# BOARD.net
KiCad netlist of a schematic drawn in EAGLE
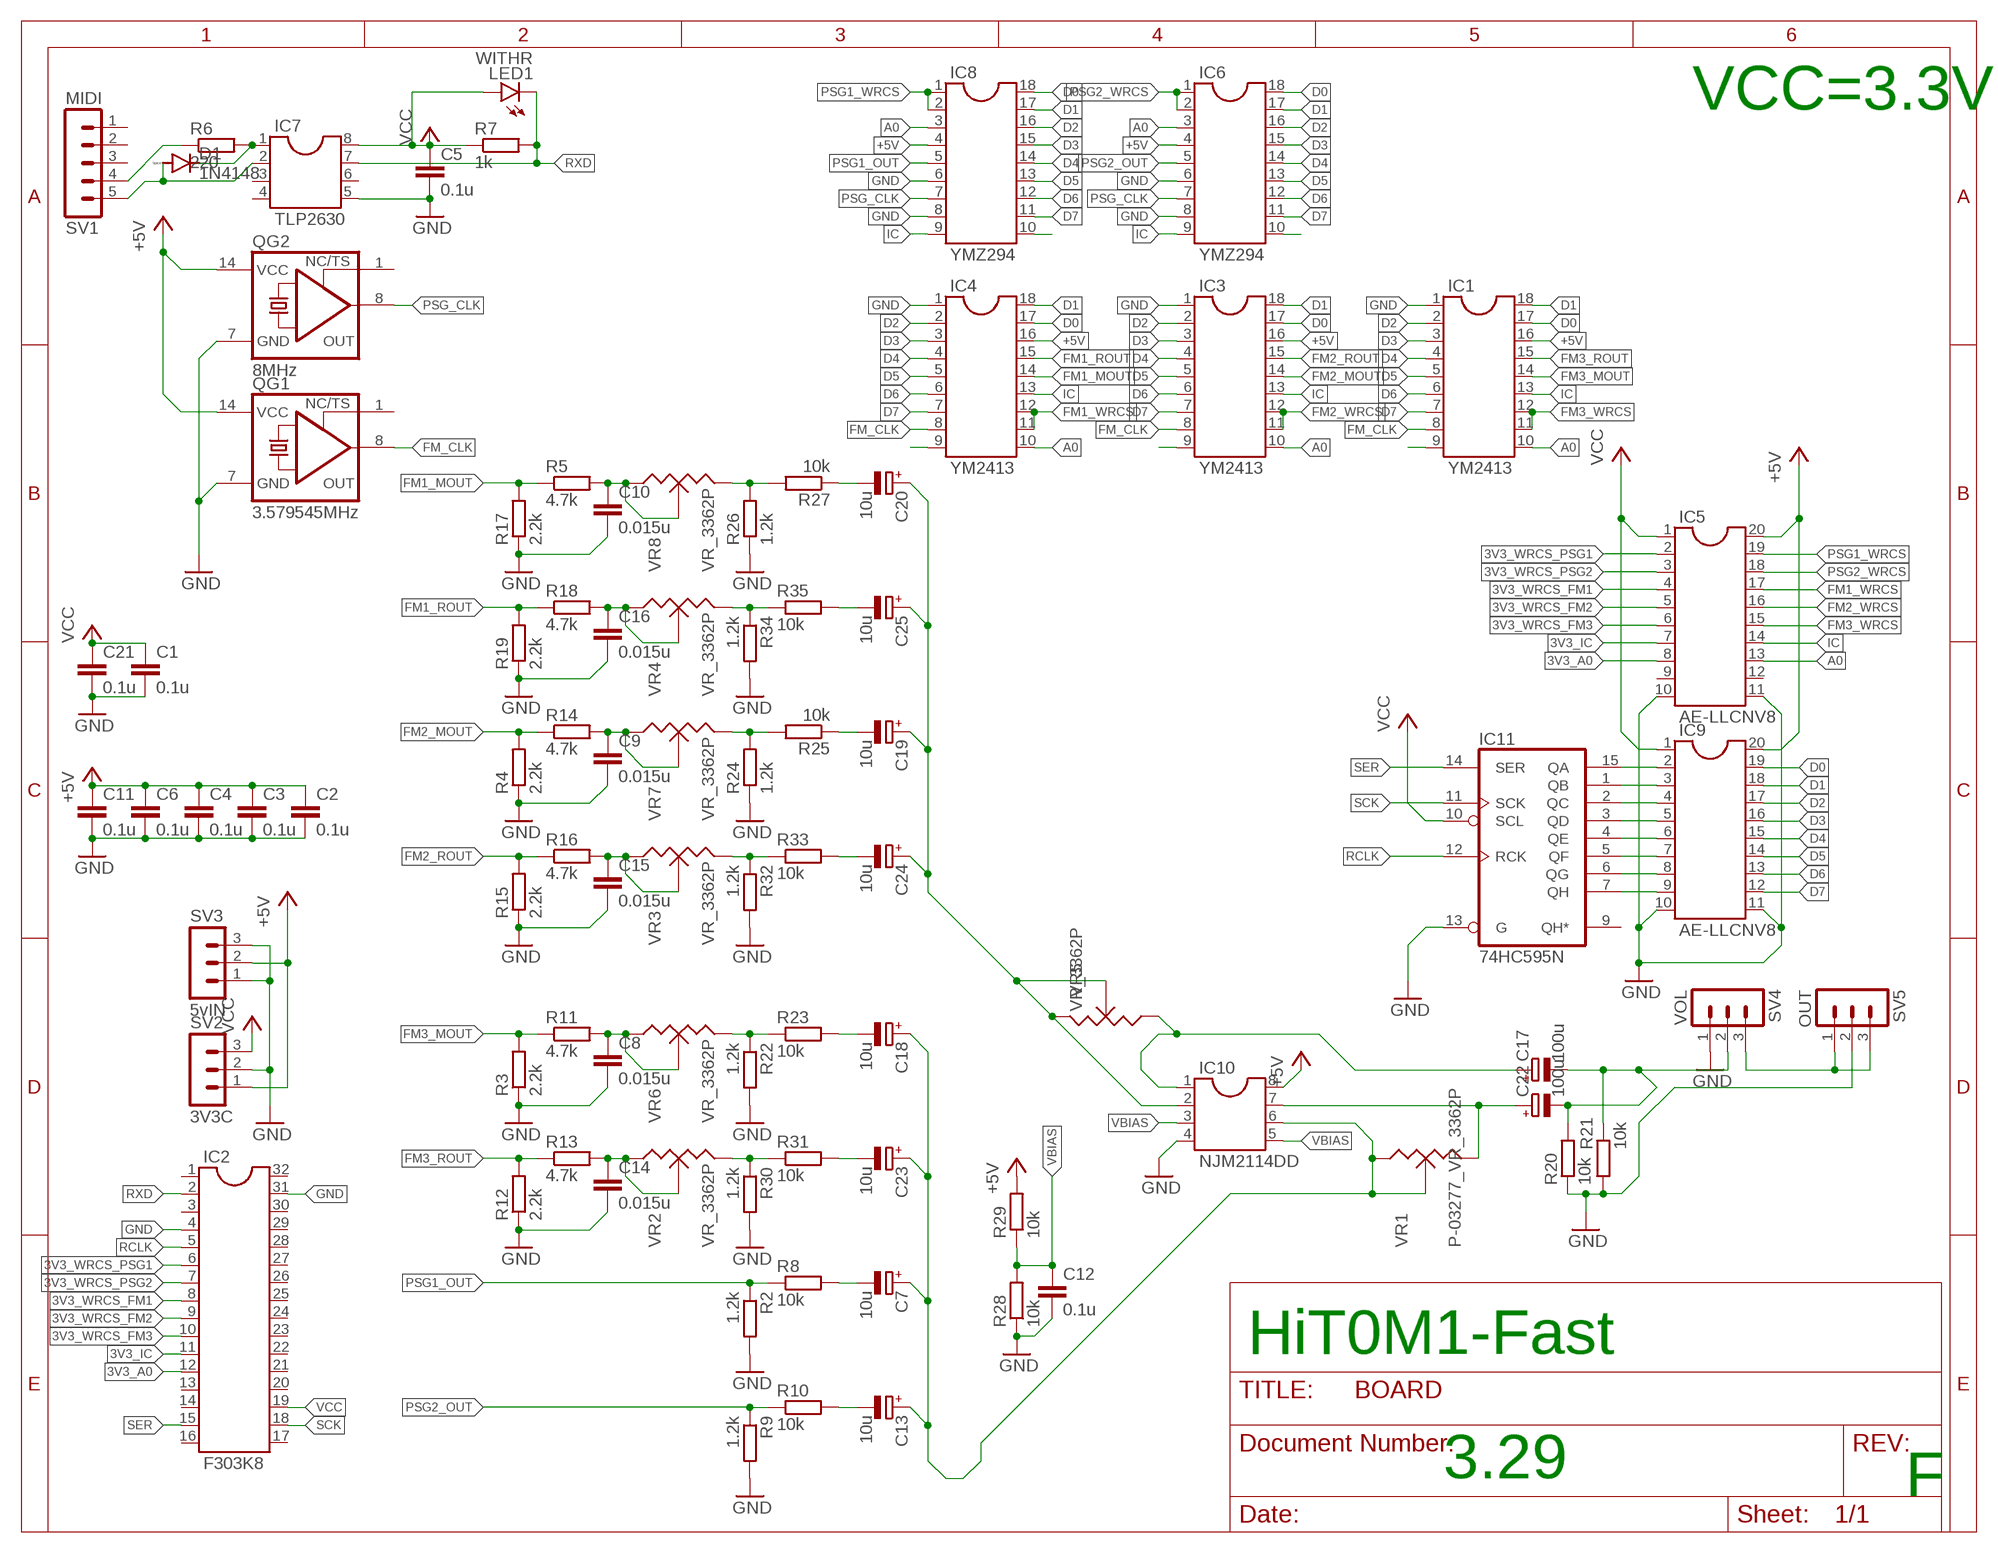
[diagram p0: schematic, sheet 1]

(export (version "E")
  (design (tool "Eeschema 10.0.6"))
  (components
    (comp (ref "C1")
      (value "0.1u")
      (footprint "eagle-import:C025-025X050")
      (libsource (lib "eagle-import") (part "C-EU025-025X050"))
    )
    (comp (ref "C2")
      (value "0.1u")
      (footprint "eagle-import:C025-025X050")
      (libsource (lib "eagle-import") (part "C-EU025-025X050"))
    )
    (comp (ref "C3")
      (value "0.1u")
      (footprint "eagle-import:C025-025X050")
      (libsource (lib "eagle-import") (part "C-EU025-025X050"))
    )
    (comp (ref "C4")
      (value "0.1u")
      (footprint "eagle-import:C025-025X050")
      (libsource (lib "eagle-import") (part "C-EU025-025X050"))
    )
    (comp (ref "C5")
      (value "0.1u")
      (footprint "eagle-import:C025-025X050")
      (libsource (lib "eagle-import") (part "C-EU025-025X050"))
    )
    (comp (ref "C6")
      (value "0.1u")
      (footprint "eagle-import:C025-025X050")
      (libsource (lib "eagle-import") (part "C-EU025-025X050"))
    )
    (comp (ref "C7")
      (value "10u")
      (footprint "eagle-import:E2,5-6E")
      (libsource (lib "eagle-import") (part "CPOL-EUE2,5-6E"))
    )
    (comp (ref "C8")
      (value "0.015u")
      (footprint "eagle-import:C050-025X075")
      (libsource (lib "eagle-import") (part "C-EU050-025X075"))
    )
    (comp (ref "C9")
      (value "0.015u")
      (footprint "eagle-import:C050-025X075")
      (libsource (lib "eagle-import") (part "C-EU050-025X075"))
    )
    (comp (ref "C10")
      (value "0.015u")
      (footprint "eagle-import:C050-025X075")
      (libsource (lib "eagle-import") (part "C-EU050-025X075"))
    )
    (comp (ref "C11")
      (value "0.1u")
      (footprint "eagle-import:C025-025X050")
      (libsource (lib "eagle-import") (part "C-EU025-025X050"))
    )
    (comp (ref "C12")
      (value "0.1u")
      (footprint "eagle-import:C025-025X050")
      (libsource (lib "eagle-import") (part "C-EU025-025X050"))
    )
    (comp (ref "C13")
      (value "10u")
      (footprint "eagle-import:E2,5-6E")
      (libsource (lib "eagle-import") (part "CPOL-EUE2,5-6E"))
    )
    (comp (ref "C14")
      (value "0.015u")
      (footprint "eagle-import:C050-025X075")
      (libsource (lib "eagle-import") (part "C-EU050-025X075"))
    )
    (comp (ref "C15")
      (value "0.015u")
      (footprint "eagle-import:C050-025X075")
      (libsource (lib "eagle-import") (part "C-EU050-025X075"))
    )
    (comp (ref "C16")
      (value "0.015u")
      (footprint "eagle-import:C050-025X075")
      (libsource (lib "eagle-import") (part "C-EU050-025X075"))
    )
    (comp (ref "C17")
      (value "100u")
      (footprint "eagle-import:E2,5-6E")
      (libsource (lib "eagle-import") (part "CPOL-EUE2,5-6E"))
    )
    (comp (ref "C18")
      (value "10u")
      (footprint "eagle-import:E2,5-6E")
      (libsource (lib "eagle-import") (part "CPOL-EUE2,5-6E"))
    )
    (comp (ref "C19")
      (value "10u")
      (footprint "eagle-import:E2,5-6E")
      (libsource (lib "eagle-import") (part "CPOL-EUE2,5-6E"))
    )
    (comp (ref "C20")
      (value "10u")
      (footprint "eagle-import:E2,5-6E")
      (libsource (lib "eagle-import") (part "CPOL-EUE2,5-6E"))
    )
    (comp (ref "C21")
      (value "0.1u")
      (footprint "eagle-import:C025-025X050")
      (libsource (lib "eagle-import") (part "C-EU025-025X050"))
    )
    (comp (ref "C22")
      (value "100u")
      (footprint "eagle-import:E2,5-6E")
      (libsource (lib "eagle-import") (part "CPOL-EUE2,5-6E"))
    )
    (comp (ref "C23")
      (value "10u")
      (footprint "eagle-import:E2,5-6E")
      (libsource (lib "eagle-import") (part "CPOL-EUE2,5-6E"))
    )
    (comp (ref "C24")
      (value "10u")
      (footprint "eagle-import:E2,5-6E")
      (libsource (lib "eagle-import") (part "CPOL-EUE2,5-6E"))
    )
    (comp (ref "C25")
      (value "10u")
      (footprint "eagle-import:E2,5-6E")
      (libsource (lib "eagle-import") (part "CPOL-EUE2,5-6E"))
    )
    (comp (ref "D1")
      (value "1N4148")
      (footprint "eagle-import:DO35-7")
      (libsource (lib "eagle-import") (part "1N4148DO35-7"))
    )
    (comp (ref "IC1")
      (value "YM2413")
      (footprint "eagle-import:SOCKET-18")
      (libsource (lib "eagle-import") (part "DIL18S"))
    )
    (comp (ref "IC2")
      (value "F303K8")
      (footprint "eagle-import:DIL32")
      (libsource (lib "eagle-import") (part "DIL32"))
    )
    (comp (ref "IC3")
      (value "YM2413")
      (footprint "eagle-import:SOCKET-18")
      (libsource (lib "eagle-import") (part "DIL18S"))
    )
    (comp (ref "IC4")
      (value "YM2413")
      (footprint "eagle-import:SOCKET-18")
      (libsource (lib "eagle-import") (part "DIL18S"))
    )
    (comp (ref "IC5")
      (value "AE-LLCNV8")
      (footprint "eagle-import:SOCKET-20")
      (libsource (lib "eagle-import") (part "DIL20S"))
    )
    (comp (ref "IC6")
      (value "YMZ294")
      (footprint "eagle-import:SOCKET-18")
      (libsource (lib "eagle-import") (part "DIL18S"))
    )
    (comp (ref "IC7")
      (value "TLP2630")
      (footprint "eagle-import:SOCKET-08")
      (libsource (lib "eagle-import") (part "DIL8S"))
    )
    (comp (ref "IC8")
      (value "YMZ294")
      (footprint "eagle-import:SOCKET-18")
      (libsource (lib "eagle-import") (part "DIL18S"))
    )
    (comp (ref "IC9")
      (value "AE-LLCNV8")
      (footprint "eagle-import:SOCKET-20")
      (libsource (lib "eagle-import") (part "DIL20S"))
    )
    (comp (ref "IC10")
      (value "NJM2114DD")
      (footprint "eagle-import:SOCKET-08")
      (libsource (lib "eagle-import") (part "DIL8S"))
    )
    (comp (ref "IC11")
      (value "74HC595N")
      (footprint "eagle-import:DIL16")
      (libsource (lib "eagle-import") (part "74595NHC"))
    )
    (comp (ref "LED1")
      (value "WITHR")
      (footprint "eagle-import:LED3MM")
      (libsource (lib "eagle-import") (part "LED3MM"))
    )
    (comp (ref "QG1")
      (value "3.579545MHz")
      (footprint "eagle-import:DIL14S")
      (libsource (lib "eagle-import") (part "XO-14"))
    )
    (comp (ref "QG2")
      (value "8MHz")
      (footprint "eagle-import:DIL14S")
      (libsource (lib "eagle-import") (part "XO-14"))
    )
    (comp (ref "R2")
      (value "1.2k")
      (footprint "eagle-import:0207_2V")
      (libsource (lib "eagle-import") (part "R-EU_0207/2V"))
    )
    (comp (ref "R3")
      (value "2.2k")
      (footprint "eagle-import:0207_2V")
      (libsource (lib "eagle-import") (part "R-EU_0207/2V"))
    )
    (comp (ref "R4")
      (value "2.2k")
      (footprint "eagle-import:0207_2V")
      (libsource (lib "eagle-import") (part "R-EU_0207/2V"))
    )
    (comp (ref "R5")
      (value "4.7k")
      (footprint "eagle-import:0207_2V")
      (libsource (lib "eagle-import") (part "R-EU_0207/2V"))
    )
    (comp (ref "R6")
      (value "220")
      (footprint "eagle-import:0207_2V")
      (libsource (lib "eagle-import") (part "R-EU_0207/2V"))
    )
    (comp (ref "R7")
      (value "1k")
      (footprint "eagle-import:0207_2V")
      (libsource (lib "eagle-import") (part "R-EU_0207/2V"))
    )
    (comp (ref "R8")
      (value "10k")
      (footprint "eagle-import:0207_2V")
      (libsource (lib "eagle-import") (part "R-EU_0207/2V"))
    )
    (comp (ref "R9")
      (value "1.2k")
      (footprint "eagle-import:0207_2V")
      (libsource (lib "eagle-import") (part "R-EU_0207/2V"))
    )
    (comp (ref "R10")
      (value "10k")
      (footprint "eagle-import:0207_2V")
      (libsource (lib "eagle-import") (part "R-EU_0207/2V"))
    )
    (comp (ref "R11")
      (value "4.7k")
      (footprint "eagle-import:0207_2V")
      (libsource (lib "eagle-import") (part "R-EU_0207/2V"))
    )
    (comp (ref "R12")
      (value "2.2k")
      (footprint "eagle-import:0207_2V")
      (libsource (lib "eagle-import") (part "R-EU_0207/2V"))
    )
    (comp (ref "R13")
      (value "4.7k")
      (footprint "eagle-import:0207_2V")
      (libsource (lib "eagle-import") (part "R-EU_0207/2V"))
    )
    (comp (ref "R14")
      (value "4.7k")
      (footprint "eagle-import:0207_2V")
      (libsource (lib "eagle-import") (part "R-EU_0207/2V"))
    )
    (comp (ref "R15")
      (value "2.2k")
      (footprint "eagle-import:0207_2V")
      (libsource (lib "eagle-import") (part "R-EU_0207/2V"))
    )
    (comp (ref "R16")
      (value "4.7k")
      (footprint "eagle-import:0207_2V")
      (libsource (lib "eagle-import") (part "R-EU_0207/2V"))
    )
    (comp (ref "R17")
      (value "2.2k")
      (footprint "eagle-import:0207_2V")
      (libsource (lib "eagle-import") (part "R-EU_0207/2V"))
    )
    (comp (ref "R18")
      (value "4.7k")
      (footprint "eagle-import:0207_2V")
      (libsource (lib "eagle-import") (part "R-EU_0207/2V"))
    )
    (comp (ref "R19")
      (value "2.2k")
      (footprint "eagle-import:0207_2V")
      (libsource (lib "eagle-import") (part "R-EU_0207/2V"))
    )
    (comp (ref "R20")
      (value "10k")
      (footprint "eagle-import:0207_2V")
      (libsource (lib "eagle-import") (part "R-EU_0207/2V"))
    )
    (comp (ref "R21")
      (value "10k")
      (footprint "eagle-import:0207_2V")
      (libsource (lib "eagle-import") (part "R-EU_0207/2V"))
    )
    (comp (ref "R22")
      (value "1.2k")
      (footprint "eagle-import:0207_2V")
      (libsource (lib "eagle-import") (part "R-EU_0207/2V"))
    )
    (comp (ref "R23")
      (value "10k")
      (footprint "eagle-import:0207_2V")
      (libsource (lib "eagle-import") (part "R-EU_0207/2V"))
    )
    (comp (ref "R24")
      (value "1.2k")
      (footprint "eagle-import:0207_2V")
      (libsource (lib "eagle-import") (part "R-EU_0207/2V"))
    )
    (comp (ref "R25")
      (value "10k")
      (footprint "eagle-import:0207_2V")
      (libsource (lib "eagle-import") (part "R-EU_0207/2V"))
    )
    (comp (ref "R26")
      (value "1.2k")
      (footprint "eagle-import:0207_2V")
      (libsource (lib "eagle-import") (part "R-EU_0207/2V"))
    )
    (comp (ref "R27")
      (value "10k")
      (footprint "eagle-import:0207_2V")
      (libsource (lib "eagle-import") (part "R-EU_0207/2V"))
    )
    (comp (ref "R28")
      (value "10k")
      (footprint "eagle-import:0207_2V")
      (libsource (lib "eagle-import") (part "R-EU_0207/2V"))
    )
    (comp (ref "R29")
      (value "10k")
      (footprint "eagle-import:0207_2V")
      (libsource (lib "eagle-import") (part "R-EU_0207/2V"))
    )
    (comp (ref "R30")
      (value "1.2k")
      (footprint "eagle-import:0207_2V")
      (libsource (lib "eagle-import") (part "R-EU_0207/2V"))
    )
    (comp (ref "R31")
      (value "10k")
      (footprint "eagle-import:0207_2V")
      (libsource (lib "eagle-import") (part "R-EU_0207/2V"))
    )
    (comp (ref "R32")
      (value "1.2k")
      (footprint "eagle-import:0207_2V")
      (libsource (lib "eagle-import") (part "R-EU_0207/2V"))
    )
    (comp (ref "R33")
      (value "10k")
      (footprint "eagle-import:0207_2V")
      (libsource (lib "eagle-import") (part "R-EU_0207/2V"))
    )
    (comp (ref "R34")
      (value "1.2k")
      (footprint "eagle-import:0207_2V")
      (libsource (lib "eagle-import") (part "R-EU_0207/2V"))
    )
    (comp (ref "R35")
      (value "10k")
      (footprint "eagle-import:0207_2V")
      (libsource (lib "eagle-import") (part "R-EU_0207/2V"))
    )
    (comp (ref "SV1")
      (value "MIDI")
      (footprint "eagle-import:MA05-1")
      (libsource (lib "eagle-import") (part "MA05-1"))
    )
    (comp (ref "SV2")
      (value "3V3C")
      (footprint "eagle-import:MA03-1")
      (libsource (lib "eagle-import") (part "MA03-1"))
    )
    (comp (ref "SV3")
      (value "5vIN")
      (footprint "eagle-import:MA03-1")
      (libsource (lib "eagle-import") (part "MA03-1"))
    )
    (comp (ref "SV4")
      (value "VOL")
      (footprint "eagle-import:MA03-1")
      (libsource (lib "eagle-import") (part "MA03-1"))
    )
    (comp (ref "SV5")
      (value "OUT")
      (footprint "eagle-import:MA03-1")
      (libsource (lib "eagle-import") (part "MA03-1"))
    )
    (comp (ref "VR1")
      (value "P-03277_VR_3362P")
      (footprint "eagle-import:VR_3362P")
      (libsource (lib "eagle-import") (part "P-03277_VR_3362P"))
    )
    (comp (ref "VR2")
      (value "VR_3362P")
      (footprint "eagle-import:VR_3362P")
      (libsource (lib "eagle-import") (part "P-03277_VR_3362P"))
    )
    (comp (ref "VR3")
      (value "VR_3362P")
      (footprint "eagle-import:VR_3362P")
      (libsource (lib "eagle-import") (part "P-03277_VR_3362P"))
    )
    (comp (ref "VR4")
      (value "VR_3362P")
      (footprint "eagle-import:VR_3362P")
      (libsource (lib "eagle-import") (part "P-03277_VR_3362P"))
    )
    (comp (ref "VR5")
      (value "VR_3362P")
      (footprint "eagle-import:VR_3362P")
      (libsource (lib "eagle-import") (part "P-03277_VR_3362P"))
    )
    (comp (ref "VR6")
      (value "VR_3362P")
      (footprint "eagle-import:VR_3362P")
      (libsource (lib "eagle-import") (part "P-03277_VR_3362P"))
    )
    (comp (ref "VR7")
      (value "VR_3362P")
      (footprint "eagle-import:VR_3362P")
      (libsource (lib "eagle-import") (part "P-03277_VR_3362P"))
    )
    (comp (ref "VR8")
      (value "VR_3362P")
      (footprint "eagle-import:VR_3362P")
      (libsource (lib "eagle-import") (part "P-03277_VR_3362P"))
    )
  )
  (nets
    (net (code "1") (name "+5V") (class "Default")
      (node (ref "C11") (pin "1") (pinfunction "1_1") (pintype "passive"))
      (node (ref "C2") (pin "1") (pinfunction "1_1") (pintype "passive"))
      (node (ref "C3") (pin "1") (pinfunction "1_1") (pintype "passive"))
      (node (ref "C4") (pin "1") (pinfunction "1_1") (pintype "passive"))
      (node (ref "C6") (pin "1") (pinfunction "1_1") (pintype "passive"))
      (node (ref "IC1") (pin "16") (pinfunction "16_16") (pintype "passive"))
      (node (ref "IC10") (pin "8") (pinfunction "8_8") (pintype "passive"))
      (node (ref "IC3") (pin "16") (pinfunction "16_16") (pintype "passive"))
      (node (ref "IC4") (pin "16") (pinfunction "16_16") (pintype "passive"))
      (node (ref "IC5") (pin "20") (pinfunction "20_20") (pintype "passive"))
      (node (ref "IC6") (pin "4") (pinfunction "4_4") (pintype "passive"))
      (node (ref "IC8") (pin "4") (pinfunction "4_4") (pintype "passive"))
      (node (ref "IC9") (pin "20") (pinfunction "20_20") (pintype "passive"))
      (node (ref "QG1") (pin "14") (pinfunction "VCC_14") (pintype "power_in"))
      (node (ref "QG2") (pin "14") (pinfunction "VCC_14") (pintype "power_in"))
      (node (ref "R29") (pin "2") (pinfunction "2_2") (pintype "passive"))
      (node (ref "SV2") (pin "1") (pinfunction "1_1") (pintype "passive"))
      (node (ref "SV3") (pin "2") (pinfunction "2_2") (pintype "passive"))
    )
    (net (code "2") (name "3V3_A0") (class "Default")
      (node (ref "IC2") (pin "12") (pinfunction "12_12") (pintype "passive"))
      (node (ref "IC5") (pin "8") (pinfunction "8_8") (pintype "passive"))
    )
    (net (code "3") (name "3V3_IC") (class "Default")
      (node (ref "IC2") (pin "11") (pinfunction "11_11") (pintype "passive"))
      (node (ref "IC5") (pin "7") (pinfunction "7_7") (pintype "passive"))
    )
    (net (code "4") (name "3V3_WRCS_FM1") (class "Default")
      (node (ref "IC2") (pin "8") (pinfunction "8_8") (pintype "passive"))
      (node (ref "IC5") (pin "4") (pinfunction "4_4") (pintype "passive"))
    )
    (net (code "5") (name "3V3_WRCS_FM2") (class "Default")
      (node (ref "IC2") (pin "9") (pinfunction "9_9") (pintype "passive"))
      (node (ref "IC5") (pin "5") (pinfunction "5_5") (pintype "passive"))
    )
    (net (code "6") (name "3V3_WRCS_FM3") (class "Default")
      (node (ref "IC2") (pin "10") (pinfunction "10_10") (pintype "passive"))
      (node (ref "IC5") (pin "6") (pinfunction "6_6") (pintype "passive"))
    )
    (net (code "7") (name "3V3_WRCS_PSG1") (class "Default")
      (node (ref "IC2") (pin "6") (pinfunction "6_6") (pintype "passive"))
      (node (ref "IC5") (pin "2") (pinfunction "2_2") (pintype "passive"))
    )
    (net (code "8") (name "3V3_WRCS_PSG2") (class "Default")
      (node (ref "IC2") (pin "7") (pinfunction "7_7") (pintype "passive"))
      (node (ref "IC5") (pin "3") (pinfunction "3_3") (pintype "passive"))
    )
    (net (code "9") (name "A0") (class "Default")
      (node (ref "IC1") (pin "10") (pinfunction "10_10") (pintype "passive"))
      (node (ref "IC3") (pin "10") (pinfunction "10_10") (pintype "passive"))
      (node (ref "IC4") (pin "10") (pinfunction "10_10") (pintype "passive"))
      (node (ref "IC5") (pin "13") (pinfunction "13_13") (pintype "passive"))
      (node (ref "IC6") (pin "3") (pinfunction "3_3") (pintype "passive"))
      (node (ref "IC8") (pin "3") (pinfunction "3_3") (pintype "passive"))
    )
    (net (code "10") (name "D0") (class "Default")
      (node (ref "IC1") (pin "17") (pinfunction "17_17") (pintype "passive"))
      (node (ref "IC3") (pin "17") (pinfunction "17_17") (pintype "passive"))
      (node (ref "IC4") (pin "17") (pinfunction "17_17") (pintype "passive"))
      (node (ref "IC6") (pin "18") (pinfunction "18_18") (pintype "passive"))
      (node (ref "IC8") (pin "18") (pinfunction "18_18") (pintype "passive"))
      (node (ref "IC9") (pin "19") (pinfunction "19_19") (pintype "passive"))
    )
    (net (code "11") (name "D1") (class "Default")
      (node (ref "IC1") (pin "18") (pinfunction "18_18") (pintype "passive"))
      (node (ref "IC3") (pin "18") (pinfunction "18_18") (pintype "passive"))
      (node (ref "IC4") (pin "18") (pinfunction "18_18") (pintype "passive"))
      (node (ref "IC6") (pin "17") (pinfunction "17_17") (pintype "passive"))
      (node (ref "IC8") (pin "17") (pinfunction "17_17") (pintype "passive"))
      (node (ref "IC9") (pin "18") (pinfunction "18_18") (pintype "passive"))
    )
    (net (code "12") (name "D2") (class "Default")
      (node (ref "IC1") (pin "2") (pinfunction "2_2") (pintype "passive"))
      (node (ref "IC3") (pin "2") (pinfunction "2_2") (pintype "passive"))
      (node (ref "IC4") (pin "2") (pinfunction "2_2") (pintype "passive"))
      (node (ref "IC6") (pin "16") (pinfunction "16_16") (pintype "passive"))
      (node (ref "IC8") (pin "16") (pinfunction "16_16") (pintype "passive"))
      (node (ref "IC9") (pin "17") (pinfunction "17_17") (pintype "passive"))
    )
    (net (code "13") (name "D3") (class "Default")
      (node (ref "IC1") (pin "3") (pinfunction "3_3") (pintype "passive"))
      (node (ref "IC3") (pin "3") (pinfunction "3_3") (pintype "passive"))
      (node (ref "IC4") (pin "3") (pinfunction "3_3") (pintype "passive"))
      (node (ref "IC6") (pin "15") (pinfunction "15_15") (pintype "passive"))
      (node (ref "IC8") (pin "15") (pinfunction "15_15") (pintype "passive"))
      (node (ref "IC9") (pin "16") (pinfunction "16_16") (pintype "passive"))
    )
    (net (code "14") (name "D4") (class "Default")
      (node (ref "IC1") (pin "4") (pinfunction "4_4") (pintype "passive"))
      (node (ref "IC3") (pin "4") (pinfunction "4_4") (pintype "passive"))
      (node (ref "IC4") (pin "4") (pinfunction "4_4") (pintype "passive"))
      (node (ref "IC6") (pin "14") (pinfunction "14_14") (pintype "passive"))
      (node (ref "IC8") (pin "14") (pinfunction "14_14") (pintype "passive"))
      (node (ref "IC9") (pin "15") (pinfunction "15_15") (pintype "passive"))
    )
    (net (code "15") (name "D5") (class "Default")
      (node (ref "IC1") (pin "5") (pinfunction "5_5") (pintype "passive"))
      (node (ref "IC3") (pin "5") (pinfunction "5_5") (pintype "passive"))
      (node (ref "IC4") (pin "5") (pinfunction "5_5") (pintype "passive"))
      (node (ref "IC6") (pin "13") (pinfunction "13_13") (pintype "passive"))
      (node (ref "IC8") (pin "13") (pinfunction "13_13") (pintype "passive"))
      (node (ref "IC9") (pin "14") (pinfunction "14_14") (pintype "passive"))
    )
    (net (code "16") (name "D6") (class "Default")
      (node (ref "IC1") (pin "6") (pinfunction "6_6") (pintype "passive"))
      (node (ref "IC3") (pin "6") (pinfunction "6_6") (pintype "passive"))
      (node (ref "IC4") (pin "6") (pinfunction "6_6") (pintype "passive"))
      (node (ref "IC6") (pin "12") (pinfunction "12_12") (pintype "passive"))
      (node (ref "IC8") (pin "12") (pinfunction "12_12") (pintype "passive"))
      (node (ref "IC9") (pin "13") (pinfunction "13_13") (pintype "passive"))
    )
    (net (code "17") (name "D7") (class "Default")
      (node (ref "IC1") (pin "7") (pinfunction "7_7") (pintype "passive"))
      (node (ref "IC3") (pin "7") (pinfunction "7_7") (pintype "passive"))
      (node (ref "IC4") (pin "7") (pinfunction "7_7") (pintype "passive"))
      (node (ref "IC6") (pin "11") (pinfunction "11_11") (pintype "passive"))
      (node (ref "IC8") (pin "11") (pinfunction "11_11") (pintype "passive"))
      (node (ref "IC9") (pin "12") (pinfunction "12_12") (pintype "passive"))
    )
    (net (code "18") (name "FM1_MOUT") (class "Default")
      (node (ref "IC4") (pin "14") (pinfunction "14_14") (pintype "passive"))
      (node (ref "R17") (pin "2") (pinfunction "2_2") (pintype "passive"))
      (node (ref "R5") (pin "1") (pinfunction "1_1") (pintype "passive"))
    )
    (net (code "19") (name "FM1_ROUT") (class "Default")
      (node (ref "IC4") (pin "15") (pinfunction "15_15") (pintype "passive"))
      (node (ref "R18") (pin "1") (pinfunction "1_1") (pintype "passive"))
      (node (ref "R19") (pin "2") (pinfunction "2_2") (pintype "passive"))
    )
    (net (code "20") (name "FM1_WRCS") (class "Default")
      (node (ref "IC4") (pin "11") (pinfunction "11_11") (pintype "passive"))
      (node (ref "IC4") (pin "12") (pinfunction "12_12") (pintype "passive"))
      (node (ref "IC5") (pin "17") (pinfunction "17_17") (pintype "passive"))
    )
    (net (code "21") (name "FM2_MOUT") (class "Default")
      (node (ref "IC3") (pin "14") (pinfunction "14_14") (pintype "passive"))
      (node (ref "R14") (pin "1") (pinfunction "1_1") (pintype "passive"))
      (node (ref "R4") (pin "2") (pinfunction "2_2") (pintype "passive"))
    )
    (net (code "22") (name "FM2_ROUT") (class "Default")
      (node (ref "IC3") (pin "15") (pinfunction "15_15") (pintype "passive"))
      (node (ref "R15") (pin "2") (pinfunction "2_2") (pintype "passive"))
      (node (ref "R16") (pin "1") (pinfunction "1_1") (pintype "passive"))
    )
    (net (code "23") (name "FM2_WRCS") (class "Default")
      (node (ref "IC3") (pin "11") (pinfunction "11_11") (pintype "passive"))
      (node (ref "IC3") (pin "12") (pinfunction "12_12") (pintype "passive"))
      (node (ref "IC5") (pin "16") (pinfunction "16_16") (pintype "passive"))
    )
    (net (code "24") (name "FM3_MOUT") (class "Default")
      (node (ref "IC1") (pin "14") (pinfunction "14_14") (pintype "passive"))
      (node (ref "R11") (pin "1") (pinfunction "1_1") (pintype "passive"))
      (node (ref "R3") (pin "2") (pinfunction "2_2") (pintype "passive"))
    )
    (net (code "25") (name "FM3_ROUT") (class "Default")
      (node (ref "IC1") (pin "15") (pinfunction "15_15") (pintype "passive"))
      (node (ref "R12") (pin "2") (pinfunction "2_2") (pintype "passive"))
      (node (ref "R13") (pin "1") (pinfunction "1_1") (pintype "passive"))
    )
    (net (code "26") (name "FM3_WRCS") (class "Default")
      (node (ref "IC1") (pin "11") (pinfunction "11_11") (pintype "passive"))
      (node (ref "IC1") (pin "12") (pinfunction "12_12") (pintype "passive"))
      (node (ref "IC5") (pin "15") (pinfunction "15_15") (pintype "passive"))
    )
    (net (code "27") (name "FM_CLK") (class "Default")
      (node (ref "IC1") (pin "8") (pinfunction "8_8") (pintype "passive"))
      (node (ref "IC3") (pin "8") (pinfunction "8_8") (pintype "passive"))
      (node (ref "IC4") (pin "8") (pinfunction "8_8") (pintype "passive"))
      (node (ref "QG1") (pin "8") (pinfunction "OUT_8") (pintype "output"))
    )
    (net (code "28") (name "GND") (class "Default")
      (node (ref "C1") (pin "2") (pinfunction "2_2") (pintype "passive"))
      (node (ref "C10") (pin "2") (pinfunction "2_2") (pintype "passive"))
      (node (ref "C11") (pin "2") (pinfunction "2_2") (pintype "passive"))
      (node (ref "C12") (pin "2") (pinfunction "2_2") (pintype "passive"))
      (node (ref "C14") (pin "2") (pinfunction "2_2") (pintype "passive"))
      (node (ref "C15") (pin "2") (pinfunction "2_2") (pintype "passive"))
      (node (ref "C16") (pin "2") (pinfunction "2_2") (pintype "passive"))
      (node (ref "C2") (pin "2") (pinfunction "2_2") (pintype "passive"))
      (node (ref "C21") (pin "2") (pinfunction "2_2") (pintype "passive"))
      (node (ref "C3") (pin "2") (pinfunction "2_2") (pintype "passive"))
      (node (ref "C4") (pin "2") (pinfunction "2_2") (pintype "passive"))
      (node (ref "C5") (pin "2") (pinfunction "2_2") (pintype "passive"))
      (node (ref "C6") (pin "2") (pinfunction "2_2") (pintype "passive"))
      (node (ref "C8") (pin "2") (pinfunction "2_2") (pintype "passive"))
      (node (ref "C9") (pin "2") (pinfunction "2_2") (pintype "passive"))
      (node (ref "IC1") (pin "1") (pinfunction "1_1") (pintype "passive"))
      (node (ref "IC10") (pin "4") (pinfunction "4_4") (pintype "passive"))
      (node (ref "IC11") (pin "13") (pinfunction "G_13") (pintype "input"))
      (node (ref "IC2") (pin "31") (pinfunction "31_31") (pintype "passive"))
      (node (ref "IC2") (pin "4") (pinfunction "4_4") (pintype "passive"))
      (node (ref "IC3") (pin "1") (pinfunction "1_1") (pintype "passive"))
      (node (ref "IC4") (pin "1") (pinfunction "1_1") (pintype "passive"))
      (node (ref "IC5") (pin "10") (pinfunction "10_10") (pintype "passive"))
      (node (ref "IC5") (pin "11") (pinfunction "11_11") (pintype "passive"))
      (node (ref "IC6") (pin "6") (pinfunction "6_6") (pintype "passive"))
      (node (ref "IC6") (pin "8") (pinfunction "8_8") (pintype "passive"))
      (node (ref "IC7") (pin "5") (pinfunction "5_5") (pintype "passive"))
      (node (ref "IC8") (pin "6") (pinfunction "6_6") (pintype "passive"))
      (node (ref "IC8") (pin "8") (pinfunction "8_8") (pintype "passive"))
      (node (ref "IC9") (pin "10") (pinfunction "10_10") (pintype "passive"))
      (node (ref "IC9") (pin "11") (pinfunction "11_11") (pintype "passive"))
      (node (ref "QG1") (pin "7") (pinfunction "GND_7") (pintype "power_in"))
      (node (ref "QG2") (pin "7") (pinfunction "GND_7") (pintype "power_in"))
      (node (ref "R12") (pin "1") (pinfunction "1_1") (pintype "passive"))
      (node (ref "R15") (pin "1") (pinfunction "1_1") (pintype "passive"))
      (node (ref "R17") (pin "1") (pinfunction "1_1") (pintype "passive"))
      (node (ref "R19") (pin "1") (pinfunction "1_1") (pintype "passive"))
      (node (ref "R2") (pin "2") (pinfunction "2_2") (pintype "passive"))
      (node (ref "R20") (pin "1") (pinfunction "1_1") (pintype "passive"))
      (node (ref "R21") (pin "1") (pinfunction "1_1") (pintype "passive"))
      (node (ref "R22") (pin "2") (pinfunction "2_2") (pintype "passive"))
      (node (ref "R24") (pin "1") (pinfunction "1_1") (pintype "passive"))
      (node (ref "R26") (pin "1") (pinfunction "1_1") (pintype "passive"))
      (node (ref "R28") (pin "1") (pinfunction "1_1") (pintype "passive"))
      (node (ref "R3") (pin "1") (pinfunction "1_1") (pintype "passive"))
      (node (ref "R30") (pin "2") (pinfunction "2_2") (pintype "passive"))
      (node (ref "R32") (pin "2") (pinfunction "2_2") (pintype "passive"))
      (node (ref "R34") (pin "2") (pinfunction "2_2") (pintype "passive"))
      (node (ref "R4") (pin "1") (pinfunction "1_1") (pintype "passive"))
      (node (ref "R9") (pin "2") (pinfunction "2_2") (pintype "passive"))
      (node (ref "SV2") (pin "2") (pinfunction "2_2") (pintype "passive"))
      (node (ref "SV3") (pin "1") (pinfunction "1_1") (pintype "passive"))
      (node (ref "SV3") (pin "3") (pinfunction "3_3") (pintype "passive"))
      (node (ref "SV4") (pin "1") (pinfunction "1_1") (pintype "passive"))
      (node (ref "SV5") (pin "2") (pinfunction "2_2") (pintype "passive"))
    )
    (net (code "29") (name "IC") (class "Default")
      (node (ref "IC1") (pin "13") (pinfunction "13_13") (pintype "passive"))
      (node (ref "IC3") (pin "13") (pinfunction "13_13") (pintype "passive"))
      (node (ref "IC4") (pin "13") (pinfunction "13_13") (pintype "passive"))
      (node (ref "IC5") (pin "14") (pinfunction "14_14") (pintype "passive"))
      (node (ref "IC6") (pin "9") (pinfunction "9_9") (pintype "passive"))
      (node (ref "IC8") (pin "9") (pinfunction "9_9") (pintype "passive"))
    )
    (net (code "30") (name "Net-(C7-Pad-)") (class "Default")
      (node (ref "C7") (pin "-") (pinfunction "-_-") (pintype "passive"))
      (node (ref "R8") (pin "2") (pinfunction "2_2") (pintype "passive"))
    )
    (net (code "31") (name "Net-(C8-Pad1)") (class "Default")
      (node (ref "C8") (pin "1") (pinfunction "1_1") (pintype "passive"))
      (node (ref "R11") (pin "2") (pinfunction "2_2") (pintype "passive"))
      (node (ref "VR6") (pin "1") (pinfunction "1_1") (pintype "bidirectional"))
      (node (ref "VR6") (pin "2") (pinfunction "2_2") (pintype "bidirectional"))
    )
    (net (code "32") (name "Net-(C9-Pad1)") (class "Default")
      (node (ref "C9") (pin "1") (pinfunction "1_1") (pintype "passive"))
      (node (ref "R14") (pin "2") (pinfunction "2_2") (pintype "passive"))
      (node (ref "VR7") (pin "1") (pinfunction "1_1") (pintype "bidirectional"))
      (node (ref "VR7") (pin "2") (pinfunction "2_2") (pintype "bidirectional"))
    )
    (net (code "33") (name "Net-(C10-Pad1)") (class "Default")
      (node (ref "C10") (pin "1") (pinfunction "1_1") (pintype "passive"))
      (node (ref "R5") (pin "2") (pinfunction "2_2") (pintype "passive"))
      (node (ref "VR8") (pin "1") (pinfunction "1_1") (pintype "bidirectional"))
      (node (ref "VR8") (pin "2") (pinfunction "2_2") (pintype "bidirectional"))
    )
    (net (code "34") (name "Net-(C13-Pad+)") (class "Default")
      (node (ref "C13") (pin "+") (pinfunction "+_+") (pintype "passive"))
      (node (ref "C18") (pin "+") (pinfunction "+_+") (pintype "passive"))
      (node (ref "C23") (pin "+") (pinfunction "+_+") (pintype "passive"))
      (node (ref "C7") (pin "+") (pinfunction "+_+") (pintype "passive"))
      (node (ref "IC10") (pin "6") (pinfunction "6_6") (pintype "passive"))
      (node (ref "VR1") (pin "1") (pinfunction "1_1") (pintype "bidirectional"))
      (node (ref "VR1") (pin "2") (pinfunction "2_2") (pintype "bidirectional"))
    )
    (net (code "35") (name "Net-(C13-Pad-)") (class "Default")
      (node (ref "C13") (pin "-") (pinfunction "-_-") (pintype "passive"))
      (node (ref "R10") (pin "2") (pinfunction "2_2") (pintype "passive"))
    )
    (net (code "36") (name "Net-(C14-Pad1)") (class "Default")
      (node (ref "C14") (pin "1") (pinfunction "1_1") (pintype "passive"))
      (node (ref "R13") (pin "2") (pinfunction "2_2") (pintype "passive"))
      (node (ref "VR2") (pin "1") (pinfunction "1_1") (pintype "bidirectional"))
      (node (ref "VR2") (pin "2") (pinfunction "2_2") (pintype "bidirectional"))
    )
    (net (code "37") (name "Net-(C15-Pad1)") (class "Default")
      (node (ref "C15") (pin "1") (pinfunction "1_1") (pintype "passive"))
      (node (ref "R16") (pin "2") (pinfunction "2_2") (pintype "passive"))
      (node (ref "VR3") (pin "1") (pinfunction "1_1") (pintype "bidirectional"))
      (node (ref "VR3") (pin "2") (pinfunction "2_2") (pintype "bidirectional"))
    )
    (net (code "38") (name "Net-(C16-Pad1)") (class "Default")
      (node (ref "C16") (pin "1") (pinfunction "1_1") (pintype "passive"))
      (node (ref "R18") (pin "2") (pinfunction "2_2") (pintype "passive"))
      (node (ref "VR4") (pin "1") (pinfunction "1_1") (pintype "bidirectional"))
      (node (ref "VR4") (pin "2") (pinfunction "2_2") (pintype "bidirectional"))
    )
    (net (code "39") (name "Net-(C17-Pad+)") (class "Default")
      (node (ref "C17") (pin "+") (pinfunction "+_+") (pintype "passive"))
      (node (ref "IC10") (pin "1") (pinfunction "1_1") (pintype "passive"))
      (node (ref "VR5") (pin "1") (pinfunction "1_1") (pintype "bidirectional"))
    )
    (net (code "40") (name "Net-(C17-Pad-)") (class "Default")
      (node (ref "C17") (pin "-") (pinfunction "-_-") (pintype "passive"))
      (node (ref "C22") (pin "-") (pinfunction "-_-") (pintype "passive"))
      (node (ref "R20") (pin "2") (pinfunction "2_2") (pintype "passive"))
      (node (ref "R21") (pin "2") (pinfunction "2_2") (pintype "passive"))
      (node (ref "SV4") (pin "2") (pinfunction "2_2") (pintype "passive"))
    )
    (net (code "41") (name "Net-(C18-Pad-)") (class "Default")
      (node (ref "C18") (pin "-") (pinfunction "-_-") (pintype "passive"))
      (node (ref "R23") (pin "2") (pinfunction "2_2") (pintype "passive"))
    )
    (net (code "42") (name "Net-(C19-Pad+)") (class "Default")
      (node (ref "C19") (pin "+") (pinfunction "+_+") (pintype "passive"))
      (node (ref "C20") (pin "+") (pinfunction "+_+") (pintype "passive"))
      (node (ref "C24") (pin "+") (pinfunction "+_+") (pintype "passive"))
      (node (ref "C25") (pin "+") (pinfunction "+_+") (pintype "passive"))
      (node (ref "IC10") (pin "2") (pinfunction "2_2") (pintype "passive"))
      (node (ref "VR5") (pin "2") (pinfunction "2_2") (pintype "bidirectional"))
      (node (ref "VR5") (pin "3") (pinfunction "3_3") (pintype "bidirectional"))
    )
    (net (code "43") (name "Net-(C19-Pad-)") (class "Default")
      (node (ref "C19") (pin "-") (pinfunction "-_-") (pintype "passive"))
      (node (ref "R25") (pin "1") (pinfunction "1_1") (pintype "passive"))
    )
    (net (code "44") (name "Net-(C20-Pad-)") (class "Default")
      (node (ref "C20") (pin "-") (pinfunction "-_-") (pintype "passive"))
      (node (ref "R27") (pin "1") (pinfunction "1_1") (pintype "passive"))
    )
    (net (code "45") (name "Net-(C22-Pad+)") (class "Default")
      (node (ref "C22") (pin "+") (pinfunction "+_+") (pintype "passive"))
      (node (ref "IC10") (pin "7") (pinfunction "7_7") (pintype "passive"))
      (node (ref "VR1") (pin "3") (pinfunction "3_3") (pintype "bidirectional"))
    )
    (net (code "46") (name "Net-(C23-Pad-)") (class "Default")
      (node (ref "C23") (pin "-") (pinfunction "-_-") (pintype "passive"))
      (node (ref "R31") (pin "2") (pinfunction "2_2") (pintype "passive"))
    )
    (net (code "47") (name "Net-(C24-Pad-)") (class "Default")
      (node (ref "C24") (pin "-") (pinfunction "-_-") (pintype "passive"))
      (node (ref "R33") (pin "2") (pinfunction "2_2") (pintype "passive"))
    )
    (net (code "48") (name "Net-(C25-Pad-)") (class "Default")
      (node (ref "C25") (pin "-") (pinfunction "-_-") (pintype "passive"))
      (node (ref "R35") (pin "2") (pinfunction "2_2") (pintype "passive"))
    )
    (net (code "49") (name "Net-(D1-PadA)") (class "Default")
      (node (ref "D1") (pin "A") (pinfunction "A_A") (pintype "passive"))
      (node (ref "IC7") (pin "2") (pinfunction "2_2") (pintype "passive"))
      (node (ref "SV1") (pin "5") (pinfunction "5_5") (pintype "passive"))
    )
    (net (code "50") (name "Net-(D1-PadC)") (class "Default")
      (node (ref "D1") (pin "C") (pinfunction "C_C") (pintype "passive"))
      (node (ref "IC7") (pin "1") (pinfunction "1_1") (pintype "passive"))
      (node (ref "R6") (pin "2") (pinfunction "2_2") (pintype "passive"))
    )
    (net (code "51") (name "Net-(IC11A-QA)") (class "Default")
      (node (ref "IC11") (pin "15") (pinfunction "QA_15") (pintype "tri_state"))
      (node (ref "IC9") (pin "2") (pinfunction "2_2") (pintype "passive"))
    )
    (net (code "52") (name "Net-(IC11A-QB)") (class "Default")
      (node (ref "IC11") (pin "1") (pinfunction "QB_1") (pintype "tri_state"))
      (node (ref "IC9") (pin "3") (pinfunction "3_3") (pintype "passive"))
    )
    (net (code "53") (name "Net-(IC11A-QC)") (class "Default")
      (node (ref "IC11") (pin "2") (pinfunction "QC_2") (pintype "tri_state"))
      (node (ref "IC9") (pin "4") (pinfunction "4_4") (pintype "passive"))
    )
    (net (code "54") (name "Net-(IC11A-QD)") (class "Default")
      (node (ref "IC11") (pin "3") (pinfunction "QD_3") (pintype "tri_state"))
      (node (ref "IC9") (pin "5") (pinfunction "5_5") (pintype "passive"))
    )
    (net (code "55") (name "Net-(IC11A-QE)") (class "Default")
      (node (ref "IC11") (pin "4") (pinfunction "QE_4") (pintype "tri_state"))
      (node (ref "IC9") (pin "6") (pinfunction "6_6") (pintype "passive"))
    )
    (net (code "56") (name "Net-(IC11A-QF)") (class "Default")
      (node (ref "IC11") (pin "5") (pinfunction "QF_5") (pintype "tri_state"))
      (node (ref "IC9") (pin "7") (pinfunction "7_7") (pintype "passive"))
    )
    (net (code "57") (name "Net-(IC11A-QG)") (class "Default")
      (node (ref "IC11") (pin "6") (pinfunction "QG_6") (pintype "tri_state"))
      (node (ref "IC9") (pin "8") (pinfunction "8_8") (pintype "passive"))
    )
    (net (code "58") (name "Net-(IC11A-QH)") (class "Default")
      (node (ref "IC11") (pin "7") (pinfunction "QH_7") (pintype "tri_state"))
      (node (ref "IC9") (pin "9") (pinfunction "9_9") (pintype "passive"))
    )
    (net (code "59") (name "Net-(R6-Pad1)") (class "Default")
      (node (ref "R6") (pin "1") (pinfunction "1_1") (pintype "passive"))
      (node (ref "SV1") (pin "4") (pinfunction "4_4") (pintype "passive"))
    )
    (net (code "60") (name "Net-(R22-Pad1)") (class "Default")
      (node (ref "R22") (pin "1") (pinfunction "1_1") (pintype "passive"))
      (node (ref "R23") (pin "1") (pinfunction "1_1") (pintype "passive"))
      (node (ref "VR6") (pin "3") (pinfunction "3_3") (pintype "bidirectional"))
    )
    (net (code "61") (name "Net-(R24-Pad2)") (class "Default")
      (node (ref "R24") (pin "2") (pinfunction "2_2") (pintype "passive"))
      (node (ref "R25") (pin "2") (pinfunction "2_2") (pintype "passive"))
      (node (ref "VR7") (pin "3") (pinfunction "3_3") (pintype "bidirectional"))
    )
    (net (code "62") (name "Net-(R26-Pad2)") (class "Default")
      (node (ref "R26") (pin "2") (pinfunction "2_2") (pintype "passive"))
      (node (ref "R27") (pin "2") (pinfunction "2_2") (pintype "passive"))
      (node (ref "VR8") (pin "3") (pinfunction "3_3") (pintype "bidirectional"))
    )
    (net (code "63") (name "Net-(R30-Pad1)") (class "Default")
      (node (ref "R30") (pin "1") (pinfunction "1_1") (pintype "passive"))
      (node (ref "R31") (pin "1") (pinfunction "1_1") (pintype "passive"))
      (node (ref "VR2") (pin "3") (pinfunction "3_3") (pintype "bidirectional"))
    )
    (net (code "64") (name "Net-(R32-Pad1)") (class "Default")
      (node (ref "R32") (pin "1") (pinfunction "1_1") (pintype "passive"))
      (node (ref "R33") (pin "1") (pinfunction "1_1") (pintype "passive"))
      (node (ref "VR3") (pin "3") (pinfunction "3_3") (pintype "bidirectional"))
    )
    (net (code "65") (name "Net-(R34-Pad1)") (class "Default")
      (node (ref "R34") (pin "1") (pinfunction "1_1") (pintype "passive"))
      (node (ref "R35") (pin "1") (pinfunction "1_1") (pintype "passive"))
      (node (ref "VR4") (pin "3") (pinfunction "3_3") (pintype "bidirectional"))
    )
    (net (code "66") (name "Net-(SV4-Pad3)") (class "Default")
      (node (ref "SV4") (pin "3") (pinfunction "3_3") (pintype "passive"))
      (node (ref "SV5") (pin "1") (pinfunction "1_1") (pintype "passive"))
      (node (ref "SV5") (pin "3") (pinfunction "3_3") (pintype "passive"))
    )
    (net (code "67") (name "PSG1_OUT") (class "Default")
      (node (ref "IC8") (pin "5") (pinfunction "5_5") (pintype "passive"))
      (node (ref "R2") (pin "1") (pinfunction "1_1") (pintype "passive"))
      (node (ref "R8") (pin "1") (pinfunction "1_1") (pintype "passive"))
    )
    (net (code "68") (name "PSG1_WRCS") (class "Default")
      (node (ref "IC5") (pin "19") (pinfunction "19_19") (pintype "passive"))
      (node (ref "IC8") (pin "1") (pinfunction "1_1") (pintype "passive"))
      (node (ref "IC8") (pin "2") (pinfunction "2_2") (pintype "passive"))
    )
    (net (code "69") (name "PSG2_OUT") (class "Default")
      (node (ref "IC6") (pin "5") (pinfunction "5_5") (pintype "passive"))
      (node (ref "R10") (pin "1") (pinfunction "1_1") (pintype "passive"))
      (node (ref "R9") (pin "1") (pinfunction "1_1") (pintype "passive"))
    )
    (net (code "70") (name "PSG2_WRCS") (class "Default")
      (node (ref "IC5") (pin "18") (pinfunction "18_18") (pintype "passive"))
      (node (ref "IC6") (pin "1") (pinfunction "1_1") (pintype "passive"))
      (node (ref "IC6") (pin "2") (pinfunction "2_2") (pintype "passive"))
    )
    (net (code "71") (name "PSG_CLK") (class "Default")
      (node (ref "IC6") (pin "7") (pinfunction "7_7") (pintype "passive"))
      (node (ref "IC8") (pin "7") (pinfunction "7_7") (pintype "passive"))
      (node (ref "QG2") (pin "8") (pinfunction "OUT_8") (pintype "output"))
    )
    (net (code "72") (name "RCLK") (class "Default")
      (node (ref "IC11") (pin "12") (pinfunction "RCK_12") (pintype "input"))
      (node (ref "IC2") (pin "5") (pinfunction "5_5") (pintype "passive"))
    )
    (net (code "73") (name "RXD") (class "Default")
      (node (ref "IC2") (pin "2") (pinfunction "2_2") (pintype "passive"))
      (node (ref "IC7") (pin "7") (pinfunction "7_7") (pintype "passive"))
      (node (ref "LED1") (pin "K") (pinfunction "C_K") (pintype "passive"))
      (node (ref "R7") (pin "2") (pinfunction "2_2") (pintype "passive"))
    )
    (net (code "74") (name "SCK") (class "Default")
      (node (ref "IC11") (pin "11") (pinfunction "SCK_11") (pintype "input"))
      (node (ref "IC2") (pin "18") (pinfunction "18_18") (pintype "passive"))
    )
    (net (code "75") (name "SER") (class "Default")
      (node (ref "IC11") (pin "14") (pinfunction "SER_14") (pintype "input"))
      (node (ref "IC2") (pin "15") (pinfunction "15_15") (pintype "passive"))
    )
    (net (code "76") (name "VBIAS") (class "Default")
      (node (ref "C12") (pin "1") (pinfunction "1_1") (pintype "passive"))
      (node (ref "IC10") (pin "3") (pinfunction "3_3") (pintype "passive"))
      (node (ref "IC10") (pin "5") (pinfunction "5_5") (pintype "passive"))
      (node (ref "R28") (pin "2") (pinfunction "2_2") (pintype "passive"))
      (node (ref "R29") (pin "1") (pinfunction "1_1") (pintype "passive"))
    )
    (net (code "77") (name "VCC") (class "Default")
      (node (ref "C1") (pin "1") (pinfunction "1_1") (pintype "passive"))
      (node (ref "C21") (pin "1") (pinfunction "1_1") (pintype "passive"))
      (node (ref "C5") (pin "1") (pinfunction "1_1") (pintype "passive"))
      (node (ref "IC11") (pin "10") (pinfunction "SCL_10") (pintype "input"))
      (node (ref "IC2") (pin "19") (pinfunction "19_19") (pintype "passive"))
      (node (ref "IC5") (pin "1") (pinfunction "1_1") (pintype "passive"))
      (node (ref "IC7") (pin "8") (pinfunction "8_8") (pintype "passive"))
      (node (ref "IC9") (pin "1") (pinfunction "1_1") (pintype "passive"))
      (node (ref "LED1") (pin "A") (pinfunction "A_A") (pintype "passive"))
      (node (ref "R7") (pin "1") (pinfunction "1_1") (pintype "passive"))
      (node (ref "SV2") (pin "3") (pinfunction "3_3") (pintype "passive"))
    )
    (net (code "78") (name "unconnected-(IC1-Pad9)") (class "Default")
      (node (ref "IC1") (pin "9") (pinfunction "9_9") (pintype "passive"))
    )
    (net (code "79") (name "unconnected-(IC2-Pad1)") (class "Default")
      (node (ref "IC2") (pin "1") (pinfunction "1_1") (pintype "passive"))
    )
    (net (code "80") (name "unconnected-(IC2-Pad3)") (class "Default")
      (node (ref "IC2") (pin "3") (pinfunction "3_3") (pintype "passive"))
    )
    (net (code "81") (name "unconnected-(IC2-Pad13)") (class "Default")
      (node (ref "IC2") (pin "13") (pinfunction "13_13") (pintype "passive"))
    )
    (net (code "82") (name "unconnected-(IC2-Pad14)") (class "Default")
      (node (ref "IC2") (pin "14") (pinfunction "14_14") (pintype "passive"))
    )
    (net (code "83") (name "unconnected-(IC2-Pad16)") (class "Default")
      (node (ref "IC2") (pin "16") (pinfunction "16_16") (pintype "passive"))
    )
    (net (code "84") (name "unconnected-(IC2-Pad17)") (class "Default")
      (node (ref "IC2") (pin "17") (pinfunction "17_17") (pintype "passive"))
    )
    (net (code "85") (name "unconnected-(IC2-Pad20)") (class "Default")
      (node (ref "IC2") (pin "20") (pinfunction "20_20") (pintype "passive"))
    )
    (net (code "86") (name "unconnected-(IC2-Pad21)") (class "Default")
      (node (ref "IC2") (pin "21") (pinfunction "21_21") (pintype "passive"))
    )
    (net (code "87") (name "unconnected-(IC2-Pad22)") (class "Default")
      (node (ref "IC2") (pin "22") (pinfunction "22_22") (pintype "passive"))
    )
    (net (code "88") (name "unconnected-(IC2-Pad23)") (class "Default")
      (node (ref "IC2") (pin "23") (pinfunction "23_23") (pintype "passive"))
    )
    (net (code "89") (name "unconnected-(IC2-Pad24)") (class "Default")
      (node (ref "IC2") (pin "24") (pinfunction "24_24") (pintype "passive"))
    )
    (net (code "90") (name "unconnected-(IC2-Pad25)") (class "Default")
      (node (ref "IC2") (pin "25") (pinfunction "25_25") (pintype "passive"))
    )
    (net (code "91") (name "unconnected-(IC2-Pad26)") (class "Default")
      (node (ref "IC2") (pin "26") (pinfunction "26_26") (pintype "passive"))
    )
    (net (code "92") (name "unconnected-(IC2-Pad27)") (class "Default")
      (node (ref "IC2") (pin "27") (pinfunction "27_27") (pintype "passive"))
    )
    (net (code "93") (name "unconnected-(IC2-Pad28)") (class "Default")
      (node (ref "IC2") (pin "28") (pinfunction "28_28") (pintype "passive"))
    )
    (net (code "94") (name "unconnected-(IC2-Pad29)") (class "Default")
      (node (ref "IC2") (pin "29") (pinfunction "29_29") (pintype "passive"))
    )
    (net (code "95") (name "unconnected-(IC2-Pad30)") (class "Default")
      (node (ref "IC2") (pin "30") (pinfunction "30_30") (pintype "passive"))
    )
    (net (code "96") (name "unconnected-(IC2-Pad32)") (class "Default")
      (node (ref "IC2") (pin "32") (pinfunction "32_32") (pintype "passive"))
    )
    (net (code "97") (name "unconnected-(IC3-Pad9)") (class "Default")
      (node (ref "IC3") (pin "9") (pinfunction "9_9") (pintype "passive"))
    )
    (net (code "98") (name "unconnected-(IC4-Pad9)") (class "Default")
      (node (ref "IC4") (pin "9") (pinfunction "9_9") (pintype "passive"))
    )
    (net (code "99") (name "unconnected-(IC5-Pad9)") (class "Default")
      (node (ref "IC5") (pin "9") (pinfunction "9_9") (pintype "passive"))
    )
    (net (code "100") (name "unconnected-(IC5-Pad12)") (class "Default")
      (node (ref "IC5") (pin "12") (pinfunction "12_12") (pintype "passive"))
    )
    (net (code "101") (name "unconnected-(IC6-Pad10)") (class "Default")
      (node (ref "IC6") (pin "10") (pinfunction "10_10") (pintype "passive"))
    )
    (net (code "102") (name "unconnected-(IC7-Pad3)") (class "Default")
      (node (ref "IC7") (pin "3") (pinfunction "3_3") (pintype "passive"))
    )
    (net (code "103") (name "unconnected-(IC7-Pad4)") (class "Default")
      (node (ref "IC7") (pin "4") (pinfunction "4_4") (pintype "passive"))
    )
    (net (code "104") (name "unconnected-(IC7-Pad6)") (class "Default")
      (node (ref "IC7") (pin "6") (pinfunction "6_6") (pintype "passive"))
    )
    (net (code "105") (name "unconnected-(IC8-Pad10)") (class "Default")
      (node (ref "IC8") (pin "10") (pinfunction "10_10") (pintype "passive"))
    )
    (net (code "106") (name "unconnected-(IC11A-QH*-Pad9)") (class "Default")
      (node (ref "IC11") (pin "9") (pinfunction "QH*_9") (pintype "tri_state"))
    )
    (net (code "107") (name "unconnected-(QG1-TS-Pad1)") (class "Default")
      (node (ref "QG1") (pin "1") (pinfunction "TS_1") (pintype "passive"))
    )
    (net (code "108") (name "unconnected-(QG2-TS-Pad1)") (class "Default")
      (node (ref "QG2") (pin "1") (pinfunction "TS_1") (pintype "passive"))
    )
    (net (code "109") (name "unconnected-(SV1-Pad1)") (class "Default")
      (node (ref "SV1") (pin "1") (pinfunction "1_1") (pintype "passive"))
    )
    (net (code "110") (name "unconnected-(SV1-Pad2)") (class "Default")
      (node (ref "SV1") (pin "2") (pinfunction "2_2") (pintype "passive"))
    )
    (net (code "111") (name "unconnected-(SV1-Pad3)") (class "Default")
      (node (ref "SV1") (pin "3") (pinfunction "3_3") (pintype "passive"))
    )
  )
)
